# Flight_Computer.net
KiCad netlist of a schematic drawn in Altium Designer
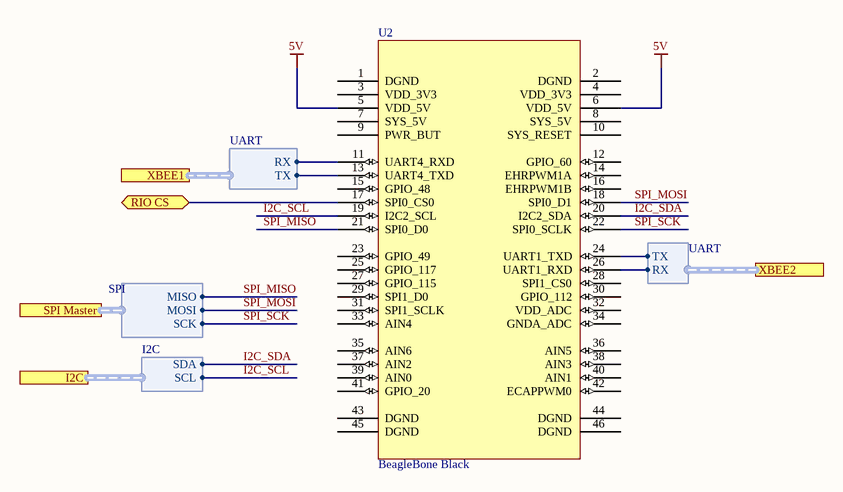
[diagram p0: Flight_Computer.SchDoc]

(export (version "E")
  (design (tool "Eeschema 10.0.6"))
  (components
    (comp (ref "U2")
      (value "BeagleBone Black")
      (footprint "BeagleBoneBlack")
      (description "P9 Header of a BeagleBone Black")
      (libsource (lib "LaunchyRIOComponents") (part "BeagleBone_Black"))
    )
  )
  (nets
    (net (code "4") (name "/I2C_SCL") (class "Default")
      (node (ref "U2") (pin "19") (pinfunction "I2C2_SCL_19") (pintype "bidirectional"))
    )
    (net (code "5") (name "/I2C_SDA") (class "Default")
      (node (ref "U2") (pin "20") (pinfunction "I2C2_SDA_20") (pintype "bidirectional"))
    )
    (net (code "6") (name "/RIO CS") (class "Default")
      (node (ref "U2") (pin "17") (pinfunction "SPI0_CS0_17") (pintype "bidirectional"))
    )
    (net (code "7") (name "/SPI_MISO") (class "Default")
      (node (ref "U2") (pin "21") (pinfunction "SPI0_D0_21") (pintype "bidirectional"))
    )
    (net (code "8") (name "/SPI_MOSI") (class "Default")
      (node (ref "U2") (pin "18") (pinfunction "SPI0_D1_18") (pintype "bidirectional"))
    )
    (net (code "9") (name "/SPI_SCK") (class "Default")
      (node (ref "U2") (pin "22") (pinfunction "SPI0_SCLK_22") (pintype "bidirectional"))
    )
    (net (code "13") (name "5V") (class "Default")
      (node (ref "U2") (pin "5") (pinfunction "VDD_5V_5") (pintype "power_in"))
      (node (ref "U2") (pin "6") (pinfunction "VDD_5V_6") (pintype "power_in"))
    )
    (net (code "14") (name "unconnected-(U2-AIN0-Pad39)") (class "Default")
      (node (ref "U2") (pin "39") (pinfunction "AIN0_39") (pintype "bidirectional"))
    )
    (net (code "15") (name "unconnected-(U2-AIN1-Pad40)") (class "Default")
      (node (ref "U2") (pin "40") (pinfunction "AIN1_40") (pintype "bidirectional"))
    )
    (net (code "16") (name "unconnected-(U2-AIN2-Pad37)") (class "Default")
      (node (ref "U2") (pin "37") (pinfunction "AIN2_37") (pintype "bidirectional"))
    )
    (net (code "17") (name "unconnected-(U2-AIN3-Pad38)") (class "Default")
      (node (ref "U2") (pin "38") (pinfunction "AIN3_38") (pintype "bidirectional"))
    )
    (net (code "18") (name "unconnected-(U2-AIN4-Pad33)") (class "Default")
      (node (ref "U2") (pin "33") (pinfunction "AIN4_33") (pintype "bidirectional"))
    )
    (net (code "19") (name "unconnected-(U2-AIN5-Pad36)") (class "Default")
      (node (ref "U2") (pin "36") (pinfunction "AIN5_36") (pintype "bidirectional"))
    )
    (net (code "20") (name "unconnected-(U2-AIN6-Pad35)") (class "Default")
      (node (ref "U2") (pin "35") (pinfunction "AIN6_35") (pintype "bidirectional"))
    )
    (net (code "21") (name "unconnected-(U2-DGND-Pad1)") (class "Default")
      (node (ref "U2") (pin "1") (pinfunction "DGND_1") (pintype "power_in"))
    )
    (net (code "22") (name "unconnected-(U2-DGND-Pad2)") (class "Default")
      (node (ref "U2") (pin "2") (pinfunction "DGND_2") (pintype "power_in"))
    )
    (net (code "23") (name "unconnected-(U2-DGND-Pad43)") (class "Default")
      (node (ref "U2") (pin "43") (pinfunction "DGND_43") (pintype "power_in"))
    )
    (net (code "24") (name "unconnected-(U2-DGND-Pad44)") (class "Default")
      (node (ref "U2") (pin "44") (pinfunction "DGND_44") (pintype "power_in"))
    )
    (net (code "25") (name "unconnected-(U2-DGND-Pad45)") (class "Default")
      (node (ref "U2") (pin "45") (pinfunction "DGND_45") (pintype "power_in"))
    )
    (net (code "26") (name "unconnected-(U2-DGND-Pad46)") (class "Default")
      (node (ref "U2") (pin "46") (pinfunction "DGND_46") (pintype "power_in"))
    )
    (net (code "27") (name "unconnected-(U2-ECAPPWM0-Pad42)") (class "Default")
      (node (ref "U2") (pin "42") (pinfunction "ECAPPWM0_42") (pintype "bidirectional"))
    )
    (net (code "28") (name "unconnected-(U2-EHRPWM1A-Pad14)") (class "Default")
      (node (ref "U2") (pin "14") (pinfunction "EHRPWM1A_14") (pintype "bidirectional"))
    )
    (net (code "29") (name "unconnected-(U2-EHRPWM1B-Pad16)") (class "Default")
      (node (ref "U2") (pin "16") (pinfunction "EHRPWM1B_16") (pintype "bidirectional"))
    )
    (net (code "30") (name "unconnected-(U2-GNDA_ADC-Pad34)") (class "Default")
      (node (ref "U2") (pin "34") (pinfunction "GNDA_ADC_34") (pintype "bidirectional"))
    )
    (net (code "31") (name "unconnected-(U2-GPIO_20-Pad41)") (class "Default")
      (node (ref "U2") (pin "41") (pinfunction "GPIO_20_41") (pintype "bidirectional"))
    )
    (net (code "32") (name "unconnected-(U2-GPIO_48-Pad15)") (class "Default")
      (node (ref "U2") (pin "15") (pinfunction "GPIO_48_15") (pintype "bidirectional"))
    )
    (net (code "33") (name "unconnected-(U2-GPIO_49-Pad23)") (class "Default")
      (node (ref "U2") (pin "23") (pinfunction "GPIO_49_23") (pintype "bidirectional"))
    )
    (net (code "34") (name "unconnected-(U2-GPIO_60-Pad12)") (class "Default")
      (node (ref "U2") (pin "12") (pinfunction "GPIO_60_12") (pintype "bidirectional"))
    )
    (net (code "35") (name "unconnected-(U2-GPIO_112-Pad30)") (class "Default")
      (node (ref "U2") (pin "30") (pinfunction "GPIO_112_30") (pintype "bidirectional"))
    )
    (net (code "36") (name "unconnected-(U2-GPIO_115-Pad27)") (class "Default")
      (node (ref "U2") (pin "27") (pinfunction "GPIO_115_27") (pintype "bidirectional"))
    )
    (net (code "37") (name "unconnected-(U2-GPIO_117-Pad25)") (class "Default")
      (node (ref "U2") (pin "25") (pinfunction "GPIO_117_25") (pintype "bidirectional"))
    )
    (net (code "38") (name "unconnected-(U2-PWR_BUT-Pad9)") (class "Default")
      (node (ref "U2") (pin "9") (pinfunction "PWR_BUT_9") (pintype "power_in"))
    )
    (net (code "39") (name "unconnected-(U2-SPI1_CS0-Pad28)") (class "Default")
      (node (ref "U2") (pin "28") (pinfunction "SPI1_CS0_28") (pintype "bidirectional"))
    )
    (net (code "40") (name "unconnected-(U2-SPI1_D0-Pad29)") (class "Default")
      (node (ref "U2") (pin "29") (pinfunction "SPI1_D0_29") (pintype "bidirectional"))
    )
    (net (code "41") (name "unconnected-(U2-SPI1_SCLK-Pad31)") (class "Default")
      (node (ref "U2") (pin "31") (pinfunction "SPI1_SCLK_31") (pintype "bidirectional"))
    )
    (net (code "42") (name "unconnected-(U2-SYS_5V-Pad7)") (class "Default")
      (node (ref "U2") (pin "7") (pinfunction "SYS_5V_7") (pintype "power_in"))
    )
    (net (code "43") (name "unconnected-(U2-SYS_5V-Pad8)") (class "Default")
      (node (ref "U2") (pin "8") (pinfunction "SYS_5V_8") (pintype "power_in"))
    )
    (net (code "44") (name "unconnected-(U2-SYS_RESET-Pad10)") (class "Default")
      (node (ref "U2") (pin "10") (pinfunction "SYS_RESET_10") (pintype "power_in"))
    )
    (net (code "45") (name "unconnected-(U2-UART1_RXD-Pad26)") (class "Default")
      (node (ref "U2") (pin "26") (pinfunction "UART1_RXD_26") (pintype "bidirectional"))
    )
    (net (code "46") (name "unconnected-(U2-UART1_TXD-Pad24)") (class "Default")
      (node (ref "U2") (pin "24") (pinfunction "UART1_TXD_24") (pintype "bidirectional"))
    )
    (net (code "47") (name "unconnected-(U2-UART4_RXD-Pad11)") (class "Default")
      (node (ref "U2") (pin "11") (pinfunction "UART4_RXD_11") (pintype "bidirectional"))
    )
    (net (code "48") (name "unconnected-(U2-UART4_TXD-Pad13)") (class "Default")
      (node (ref "U2") (pin "13") (pinfunction "UART4_TXD_13") (pintype "bidirectional"))
    )
    (net (code "49") (name "unconnected-(U2-VDD_3V3-Pad3)") (class "Default")
      (node (ref "U2") (pin "3") (pinfunction "VDD_3V3_3") (pintype "power_in"))
    )
    (net (code "50") (name "unconnected-(U2-VDD_3V3-Pad4)") (class "Default")
      (node (ref "U2") (pin "4") (pinfunction "VDD_3V3_4") (pintype "power_in"))
    )
    (net (code "51") (name "unconnected-(U2-VDD_ADC-Pad32)") (class "Default")
      (node (ref "U2") (pin "32") (pinfunction "VDD_ADC_32") (pintype "bidirectional"))
    )
  )
)
